# ID_logic.net
KiCad netlist of a schematic drawn in Altium Designer
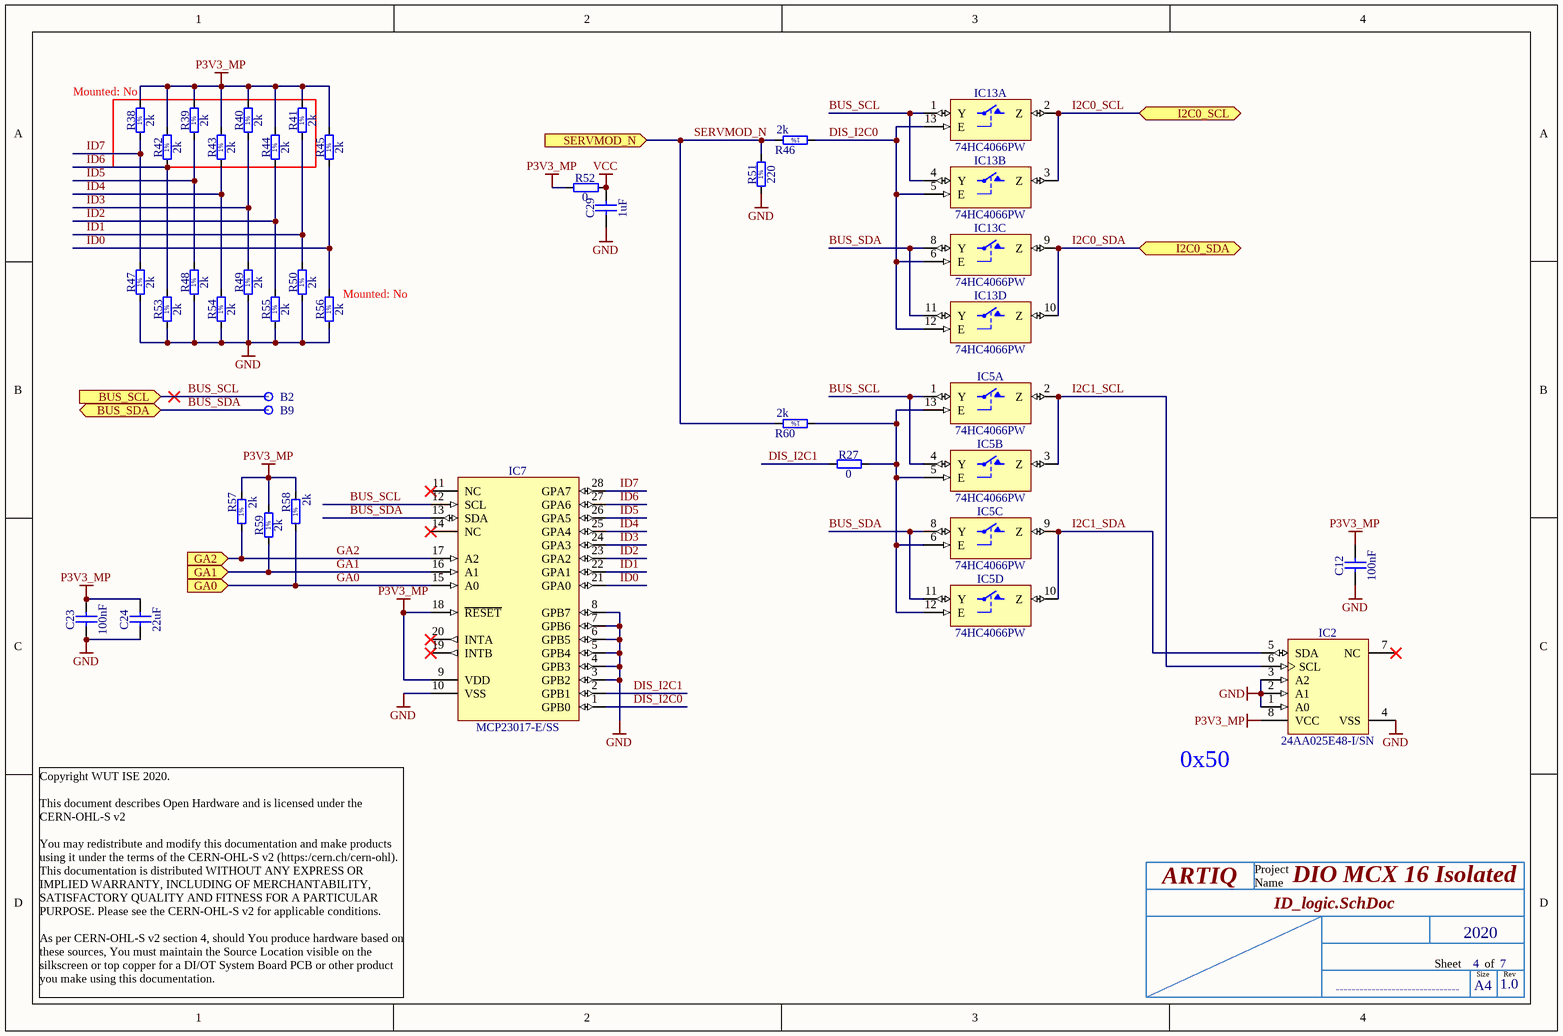
[diagram p0: ID_logic.SchDoc]

(export (version "E")
  (design (tool "Eeschema 10.0.6"))
  (components
    (comp (ref "B2")
      (value "Plated Hole")
      (footprint "c130h60")
      (description "Single Terminal Socket")
      (fields (field (name "PART NUMBER") "PLATED_HOLE0.6_PAD1.3") (field (name "AUTHOR") "CERN DEM MR"))
      (libsource (lib "Eletro-mechanical") (part "Single Terminal Socket"))
    )
    (comp (ref "B9")
      (value "Plated Hole")
      (footprint "c130h60")
      (description "Single Terminal Socket")
      (fields (field (name "PART NUMBER") "PLATED_HOLE0.6_PAD1.3") (field (name "AUTHOR") "CERN DEM MR"))
      (libsource (lib "Eletro-mechanical") (part "Single Terminal Socket"))
    )
    (comp (ref "C12")
      (value "100nF")
      (footprint "CAPC1005X55N")
      (description "Non-polarised capacitor")
      (fields
        (field (name "PART NUMBER") "CC0402_100NF_16V_10%_X5R")
        (field (name "VOLTAGE") "16V")
        (field (name "AUTHOR") "CERN DEM JLC")
      )
      (libsource (lib "Capacitors") (part "Capacitor - non polarized"))
    )
    (comp (ref "C23")
      (value "100nF")
      (footprint "CAPC1005X55N")
      (description "Non-polarised capacitor")
      (fields
        (field (name "PART NUMBER") "CC0402_100NF_16V_10%_X5R")
        (field (name "VOLTAGE") "16V")
        (field (name "AUTHOR") "CERN DEM JLC")
      )
      (libsource (lib "Capacitors") (part "Capacitor - non polarized"))
    )
    (comp (ref "C24")
      (value "22uF")
      (footprint "CAPC1709X100N")
      (description "Non-polarised capacitor")
      (fields
        (field (name "PART NUMBER") "CC0603_22UF_6.3V_20%_X5R")
        (field (name "VOLTAGE") "6.3V")
        (field (name "AUTHOR") "CERN DEM JLC")
      )
      (libsource (lib "Capacitors") (part "Capacitor - non polarized"))
    )
    (comp (ref "C29")
      (value "1uF")
      (footprint "CAPC2012X140N")
      (description "Non-polarised capacitor")
      (fields
        (field (name "PART NUMBER") "CC0805_1UF_35V_20%_X7R")
        (field (name "VOLTAGE") "35V")
        (field (name "AUTHOR") "CERN DEM JLC")
      )
      (libsource (lib "Capacitors") (part "Capacitor - non polarized"))
    )
    (comp (ref "IC2")
      (value "24AA025E48-I/SN")
      (footprint "SOIC127P600X175-8N")
      (description "1.7V-5.5V, 2K I2C™ Serial EEPROMs with EUI-48™ Node Identity")
      (fields (field (name "MANUFACTURER") "MICROCHIP TECHNOLOGY") (field (name "AUTHOR") "CERN DEM MR"))
      (libsource (lib "ICs And Semiconductors") (part "24AA025E48-I/SN"))
    )
    (comp (ref "IC5")
      (value "74HC4066PW")
      (footprint "SOP65P640X110-14N")
      (fields (field (name "MANUFACTURER") "NXP SEMICONDUCTORS") (field (name "AUTHOR") "CERN DEM JLC"))
      (libsource (lib "ICs And Semiconductors") (part "4066"))
    )
    (comp (ref "IC7")
      (value "MCP23017-E/SS")
      (footprint "SOP65P780X200-28N")
      (description "16-bit I/O Port Expander With Serial Interface")
      (fields (field (name "MANUFACTURER") "MICROCHIP TECHNOLOGY") (field (name "AUTHOR") "CERN DEM JLC"))
      (libsource (lib "ICs And Semiconductors") (part "MCP23017-E/SS"))
    )
    (comp (ref "IC13")
      (value "74HC4066PW")
      (footprint "SOP65P640X110-14N")
      (fields (field (name "MANUFACTURER") "NXP SEMICONDUCTORS") (field (name "AUTHOR") "CERN DEM JLC"))
      (libsource (lib "ICs And Semiconductors") (part "4066"))
    )
    (comp (ref "R27")
      (value "0")
      (footprint "RESC1005X40N")
      (description "Resistor")
      (fields
        (field (name "PART NUMBER") "R0402_0R_JUMPER")
        (field (name "MANUFACTURER") "GENERIC")
        (field (name "AUTHOR") "CERN DEM JLC")
      )
      (libsource (lib "Resistors") (part "Resistor"))
    )
    (comp (ref "R38")
      (value "2k")
      (footprint "RESC1608X55N")
      (description "Resistor - 1%")
      (fields
        (field (name "PART NUMBER") "R0603_2K_1%_0.1W_100PPM")
        (field (name "POWER") "0.1W")
        (field (name "MOUNTED") "No")
        (field (name "AUTHOR") "CERN DEM JLC")
      )
      (libsource (lib "Resistors") (part "Resistor - 1%"))
    )
    (comp (ref "R39")
      (value "2k")
      (footprint "RESC1608X55N")
      (description "Resistor - 1%")
      (fields
        (field (name "PART NUMBER") "R0603_2K_1%_0.1W_100PPM")
        (field (name "POWER") "0.1W")
        (field (name "AUTHOR") "CERN DEM JLC")
      )
      (libsource (lib "Resistors") (part "Resistor - 1%"))
    )
    (comp (ref "R40")
      (value "2k")
      (footprint "RESC1608X55N")
      (description "Resistor - 1%")
      (fields
        (field (name "PART NUMBER") "R0603_2K_1%_0.1W_100PPM")
        (field (name "POWER") "0.1W")
        (field (name "AUTHOR") "CERN DEM JLC")
      )
      (libsource (lib "Resistors") (part "Resistor - 1%"))
    )
    (comp (ref "R41")
      (value "2k")
      (footprint "RESC1608X55N")
      (description "Resistor - 1%")
      (fields
        (field (name "PART NUMBER") "R0603_2K_1%_0.1W_100PPM")
        (field (name "POWER") "0.1W")
        (field (name "AUTHOR") "CERN DEM JLC")
      )
      (libsource (lib "Resistors") (part "Resistor - 1%"))
    )
    (comp (ref "R42")
      (value "2k")
      (footprint "RESC1608X55N")
      (description "Resistor - 1%")
      (fields
        (field (name "PART NUMBER") "R0603_2K_1%_0.1W_100PPM")
        (field (name "POWER") "0.1W")
        (field (name "AUTHOR") "CERN DEM JLC")
      )
      (libsource (lib "Resistors") (part "Resistor - 1%"))
    )
    (comp (ref "R43")
      (value "2k")
      (footprint "RESC1608X55N")
      (description "Resistor - 1%")
      (fields
        (field (name "PART NUMBER") "R0603_2K_1%_0.1W_100PPM")
        (field (name "POWER") "0.1W")
        (field (name "AUTHOR") "CERN DEM JLC")
      )
      (libsource (lib "Resistors") (part "Resistor - 1%"))
    )
    (comp (ref "R44")
      (value "2k")
      (footprint "RESC1608X55N")
      (description "Resistor - 1%")
      (fields
        (field (name "PART NUMBER") "R0603_2K_1%_0.1W_100PPM")
        (field (name "POWER") "0.1W")
        (field (name "AUTHOR") "CERN DEM JLC")
      )
      (libsource (lib "Resistors") (part "Resistor - 1%"))
    )
    (comp (ref "R45")
      (value "2k")
      (footprint "RESC1608X55N")
      (description "Resistor - 1%")
      (fields
        (field (name "PART NUMBER") "R0603_2K_1%_0.1W_100PPM")
        (field (name "POWER") "0.1W")
        (field (name "AUTHOR") "CERN DEM JLC")
      )
      (libsource (lib "Resistors") (part "Resistor - 1%"))
    )
    (comp (ref "R46")
      (value "2k")
      (footprint "RESC1608X55N")
      (description "Resistor - 1%")
      (fields
        (field (name "PART NUMBER") "R0603_2K_1%_0.1W_100PPM")
        (field (name "POWER") "0.1W")
        (field (name "AUTHOR") "CERN DEM JLC")
      )
      (libsource (lib "Resistors") (part "Resistor - 1%"))
    )
    (comp (ref "R47")
      (value "2k")
      (footprint "RESC1608X55N")
      (description "Resistor - 1%")
      (fields
        (field (name "PART NUMBER") "R0603_2K_1%_0.1W_100PPM")
        (field (name "POWER") "0.1W")
        (field (name "AUTHOR") "CERN DEM JLC")
      )
      (libsource (lib "Resistors") (part "Resistor - 1%"))
    )
    (comp (ref "R48")
      (value "2k")
      (footprint "RESC1608X55N")
      (description "Resistor - 1%")
      (fields
        (field (name "PART NUMBER") "R0603_2K_1%_0.1W_100PPM")
        (field (name "POWER") "0.1W")
        (field (name "AUTHOR") "CERN DEM JLC")
      )
      (libsource (lib "Resistors") (part "Resistor - 1%"))
    )
    (comp (ref "R49")
      (value "2k")
      (footprint "RESC1608X55N")
      (description "Resistor - 1%")
      (fields
        (field (name "PART NUMBER") "R0603_2K_1%_0.1W_100PPM")
        (field (name "POWER") "0.1W")
        (field (name "AUTHOR") "CERN DEM JLC")
      )
      (libsource (lib "Resistors") (part "Resistor - 1%"))
    )
    (comp (ref "R50")
      (value "2k")
      (footprint "RESC1608X55N")
      (description "Resistor - 1%")
      (fields
        (field (name "PART NUMBER") "R0603_2K_1%_0.1W_100PPM")
        (field (name "POWER") "0.1W")
        (field (name "AUTHOR") "CERN DEM JLC")
      )
      (libsource (lib "Resistors") (part "Resistor - 1%"))
    )
    (comp (ref "R51")
      (value "220")
      (footprint "RESC1608X55N")
      (description "Resistor - 1%")
      (fields
        (field (name "PART NUMBER") "R0603_220R_1%_0.1W_100PPM")
        (field (name "POWER") "0.1W")
        (field (name "AUTHOR") "CERN DEM JLC")
      )
      (libsource (lib "Resistors") (part "Resistor - 1%"))
    )
    (comp (ref "R52")
      (value "0")
      (footprint "RESC1005X40N")
      (description "Resistor")
      (fields
        (field (name "PART NUMBER") "R0402_0R_JUMPER")
        (field (name "MANUFACTURER") "GENERIC")
        (field (name "AUTHOR") "CERN DEM JLC")
      )
      (libsource (lib "Resistors") (part "Resistor"))
    )
    (comp (ref "R53")
      (value "2k")
      (footprint "RESC1608X55N")
      (description "Resistor - 1%")
      (fields
        (field (name "PART NUMBER") "R0603_2K_1%_0.1W_100PPM")
        (field (name "POWER") "0.1W")
        (field (name "AUTHOR") "CERN DEM JLC")
      )
      (libsource (lib "Resistors") (part "Resistor - 1%"))
    )
    (comp (ref "R54")
      (value "2k")
      (footprint "RESC1608X55N")
      (description "Resistor - 1%")
      (fields
        (field (name "PART NUMBER") "R0603_2K_1%_0.1W_100PPM")
        (field (name "POWER") "0.1W")
        (field (name "AUTHOR") "CERN DEM JLC")
      )
      (libsource (lib "Resistors") (part "Resistor - 1%"))
    )
    (comp (ref "R55")
      (value "2k")
      (footprint "RESC1608X55N")
      (description "Resistor - 1%")
      (fields
        (field (name "PART NUMBER") "R0603_2K_1%_0.1W_100PPM")
        (field (name "POWER") "0.1W")
        (field (name "AUTHOR") "CERN DEM JLC")
      )
      (libsource (lib "Resistors") (part "Resistor - 1%"))
    )
    (comp (ref "R56")
      (value "2k")
      (footprint "RESC1608X55N")
      (description "Resistor - 1%")
      (fields
        (field (name "PART NUMBER") "R0603_2K_1%_0.1W_100PPM")
        (field (name "POWER") "0.1W")
        (field (name "MOUNTED") "No")
        (field (name "AUTHOR") "CERN DEM JLC")
      )
      (libsource (lib "Resistors") (part "Resistor - 1%"))
    )
    (comp (ref "R57")
      (value "2k")
      (footprint "RESC1608X55N")
      (description "Resistor - 1%")
      (fields
        (field (name "PART NUMBER") "R0603_2K_1%_0.1W_100PPM")
        (field (name "POWER") "0.1W")
        (field (name "AUTHOR") "CERN DEM JLC")
      )
      (libsource (lib "Resistors") (part "Resistor - 1%"))
    )
    (comp (ref "R58")
      (value "2k")
      (footprint "RESC1608X55N")
      (description "Resistor - 1%")
      (fields
        (field (name "PART NUMBER") "R0603_2K_1%_0.1W_100PPM")
        (field (name "POWER") "0.1W")
        (field (name "AUTHOR") "CERN DEM JLC")
      )
      (libsource (lib "Resistors") (part "Resistor - 1%"))
    )
    (comp (ref "R59")
      (value "2k")
      (footprint "RESC1608X55N")
      (description "Resistor - 1%")
      (fields
        (field (name "PART NUMBER") "R0603_2K_1%_0.1W_100PPM")
        (field (name "POWER") "0.1W")
        (field (name "AUTHOR") "CERN DEM JLC")
      )
      (libsource (lib "Resistors") (part "Resistor - 1%"))
    )
    (comp (ref "R60")
      (value "2k")
      (footprint "RESC1608X55N")
      (description "Resistor - 1%")
      (fields
        (field (name "PART NUMBER") "R0603_2K_1%_0.1W_100PPM")
        (field (name "POWER") "0.1W")
        (field (name "AUTHOR") "CERN DEM JLC")
      )
      (libsource (lib "Resistors") (part "Resistor - 1%"))
    )
  )
  (nets
    (net (code "1") (name "/BUS_SCL") (class "Default")
      (node (ref "B2") (pin "1") (pinfunction "1_1") (pintype "bidirectional"))
      (node (ref "IC13") (pin "1") (pinfunction "Y_1") (pintype "bidirectional"))
      (node (ref "IC13") (pin "4") (pinfunction "Y_4") (pintype "bidirectional"))
      (node (ref "IC5") (pin "1") (pinfunction "Y_1") (pintype "bidirectional"))
      (node (ref "IC5") (pin "4") (pinfunction "Y_4") (pintype "bidirectional"))
      (node (ref "IC7") (pin "12") (pinfunction "SCL_12") (pintype "input"))
    )
    (net (code "2") (name "/BUS_SDA") (class "Default")
      (node (ref "B9") (pin "1") (pinfunction "1_1") (pintype "bidirectional"))
      (node (ref "IC13") (pin "11") (pinfunction "Y_11") (pintype "bidirectional"))
      (node (ref "IC13") (pin "8") (pinfunction "Y_8") (pintype "bidirectional"))
      (node (ref "IC5") (pin "11") (pinfunction "Y_11") (pintype "bidirectional"))
      (node (ref "IC5") (pin "8") (pinfunction "Y_8") (pintype "bidirectional"))
      (node (ref "IC7") (pin "13") (pinfunction "SDA_13") (pintype "bidirectional"))
    )
    (net (code "3") (name "/DIS_I2C0") (class "Default")
      (node (ref "IC13") (pin "12") (pinfunction "E_12") (pintype "input"))
      (node (ref "IC13") (pin "13") (pinfunction "E_13") (pintype "input"))
      (node (ref "IC13") (pin "5") (pinfunction "E_5") (pintype "input"))
      (node (ref "IC13") (pin "6") (pinfunction "E_6") (pintype "input"))
      (node (ref "IC7") (pin "1") (pinfunction "GPB0_1") (pintype "bidirectional"))
      (node (ref "R46") (pin "1") (pinfunction "1_1") (pintype "passive"))
    )
    (net (code "4") (name "/DIS_I2C1") (class "Default")
      (node (ref "IC7") (pin "2") (pinfunction "GPB1_2") (pintype "bidirectional"))
      (node (ref "R27") (pin "1") (pinfunction "1_1") (pintype "passive"))
    )
    (net (code "5") (name "/GA0") (class "Default")
      (node (ref "IC7") (pin "15") (pinfunction "A0_15") (pintype "input"))
      (node (ref "R58") (pin "1") (pinfunction "1_1") (pintype "passive"))
    )
    (net (code "6") (name "/GA1") (class "Default")
      (node (ref "IC7") (pin "16") (pinfunction "A1_16") (pintype "input"))
      (node (ref "R59") (pin "1") (pinfunction "1_1") (pintype "passive"))
    )
    (net (code "7") (name "/GA2") (class "Default")
      (node (ref "IC7") (pin "17") (pinfunction "A2_17") (pintype "input"))
      (node (ref "R57") (pin "1") (pinfunction "1_1") (pintype "passive"))
    )
    (net (code "8") (name "/I2C0_SCL") (class "Default")
      (node (ref "IC13") (pin "2") (pinfunction "Z_2") (pintype "bidirectional"))
      (node (ref "IC13") (pin "3") (pinfunction "Z_3") (pintype "bidirectional"))
    )
    (net (code "9") (name "/I2C0_SDA") (class "Default")
      (node (ref "IC13") (pin "10") (pinfunction "Z_10") (pintype "bidirectional"))
      (node (ref "IC13") (pin "9") (pinfunction "Z_9") (pintype "bidirectional"))
    )
    (net (code "10") (name "/I2C1_SCL") (class "Default")
      (node (ref "IC2") (pin "6") (pinfunction "SCL_6") (pintype "input"))
      (node (ref "IC5") (pin "2") (pinfunction "Z_2") (pintype "bidirectional"))
      (node (ref "IC5") (pin "3") (pinfunction "Z_3") (pintype "bidirectional"))
    )
    (net (code "11") (name "/I2C1_SDA") (class "Default")
      (node (ref "IC2") (pin "5") (pinfunction "SDA_5") (pintype "bidirectional"))
      (node (ref "IC5") (pin "10") (pinfunction "Z_10") (pintype "bidirectional"))
      (node (ref "IC5") (pin "9") (pinfunction "Z_9") (pintype "bidirectional"))
    )
    (net (code "12") (name "/ID0") (class "Default")
      (node (ref "IC7") (pin "21") (pinfunction "GPA0_21") (pintype "bidirectional"))
      (node (ref "R45") (pin "1") (pinfunction "1_1") (pintype "passive"))
      (node (ref "R56") (pin "2") (pinfunction "2_2") (pintype "passive"))
    )
    (net (code "13") (name "/ID1") (class "Default")
      (node (ref "IC7") (pin "22") (pinfunction "GPA1_22") (pintype "bidirectional"))
      (node (ref "R41") (pin "1") (pinfunction "1_1") (pintype "passive"))
      (node (ref "R50") (pin "2") (pinfunction "2_2") (pintype "passive"))
    )
    (net (code "14") (name "/ID2") (class "Default")
      (node (ref "IC7") (pin "23") (pinfunction "GPA2_23") (pintype "bidirectional"))
      (node (ref "R44") (pin "1") (pinfunction "1_1") (pintype "passive"))
      (node (ref "R55") (pin "2") (pinfunction "2_2") (pintype "passive"))
    )
    (net (code "15") (name "/ID3") (class "Default")
      (node (ref "IC7") (pin "24") (pinfunction "GPA3_24") (pintype "bidirectional"))
      (node (ref "R40") (pin "1") (pinfunction "1_1") (pintype "passive"))
      (node (ref "R49") (pin "2") (pinfunction "2_2") (pintype "passive"))
    )
    (net (code "16") (name "/ID4") (class "Default")
      (node (ref "IC7") (pin "25") (pinfunction "GPA4_25") (pintype "bidirectional"))
      (node (ref "R43") (pin "1") (pinfunction "1_1") (pintype "passive"))
      (node (ref "R54") (pin "2") (pinfunction "2_2") (pintype "passive"))
    )
    (net (code "17") (name "/ID5") (class "Default")
      (node (ref "IC7") (pin "26") (pinfunction "GPA5_26") (pintype "bidirectional"))
      (node (ref "R39") (pin "1") (pinfunction "1_1") (pintype "passive"))
      (node (ref "R48") (pin "2") (pinfunction "2_2") (pintype "passive"))
    )
    (net (code "18") (name "/ID6") (class "Default")
      (node (ref "IC7") (pin "27") (pinfunction "GPA6_27") (pintype "bidirectional"))
      (node (ref "R42") (pin "1") (pinfunction "1_1") (pintype "passive"))
      (node (ref "R53") (pin "2") (pinfunction "2_2") (pintype "passive"))
    )
    (net (code "19") (name "/ID7") (class "Default")
      (node (ref "IC7") (pin "28") (pinfunction "GPA7_28") (pintype "bidirectional"))
      (node (ref "R38") (pin "1") (pinfunction "1_1") (pintype "passive"))
      (node (ref "R47") (pin "2") (pinfunction "2_2") (pintype "passive"))
    )
    (net (code "20") (name "/SERVMOD_N") (class "Default")
      (node (ref "R46") (pin "2") (pinfunction "2_2") (pintype "passive"))
      (node (ref "R51") (pin "2") (pinfunction "2_2") (pintype "passive"))
      (node (ref "R60") (pin "2") (pinfunction "2_2") (pintype "passive"))
    )
    (net (code "21") (name "GND") (class "Default")
      (node (ref "C12") (pin "1") (pinfunction "1_1") (pintype "passive"))
      (node (ref "C23") (pin "1") (pinfunction "1_1") (pintype "passive"))
      (node (ref "C24") (pin "1") (pinfunction "1_1") (pintype "passive"))
      (node (ref "C29") (pin "1") (pinfunction "1_1") (pintype "passive"))
      (node (ref "IC13") (pin "7") (pinfunction "GND_7") (pintype "power_in"))
      (node (ref "IC2") (pin "1") (pinfunction "A0_1") (pintype "input"))
      (node (ref "IC2") (pin "2") (pinfunction "A1_2") (pintype "input"))
      (node (ref "IC2") (pin "3") (pinfunction "A2_3") (pintype "input"))
      (node (ref "IC2") (pin "4") (pinfunction "VSS_4") (pintype "power_in"))
      (node (ref "IC5") (pin "7") (pinfunction "GND_7") (pintype "power_in"))
      (node (ref "IC7") (pin "10") (pinfunction "VSS_10") (pintype "power_in"))
      (node (ref "IC7") (pin "3") (pinfunction "GPB2_3") (pintype "bidirectional"))
      (node (ref "IC7") (pin "4") (pinfunction "GPB3_4") (pintype "bidirectional"))
      (node (ref "IC7") (pin "5") (pinfunction "GPB4_5") (pintype "bidirectional"))
      (node (ref "IC7") (pin "6") (pinfunction "GPB5_6") (pintype "bidirectional"))
      (node (ref "IC7") (pin "7") (pinfunction "GPB6_7") (pintype "bidirectional"))
      (node (ref "IC7") (pin "8") (pinfunction "GPB7_8") (pintype "bidirectional"))
      (node (ref "R47") (pin "1") (pinfunction "1_1") (pintype "passive"))
      (node (ref "R48") (pin "1") (pinfunction "1_1") (pintype "passive"))
      (node (ref "R49") (pin "1") (pinfunction "1_1") (pintype "passive"))
      (node (ref "R50") (pin "1") (pinfunction "1_1") (pintype "passive"))
      (node (ref "R51") (pin "1") (pinfunction "1_1") (pintype "passive"))
      (node (ref "R53") (pin "1") (pinfunction "1_1") (pintype "passive"))
      (node (ref "R54") (pin "1") (pinfunction "1_1") (pintype "passive"))
      (node (ref "R55") (pin "1") (pinfunction "1_1") (pintype "passive"))
      (node (ref "R56") (pin "1") (pinfunction "1_1") (pintype "passive"))
    )
    (net (code "22") (name "Net-(IC5A-E)") (class "Default")
      (node (ref "IC5") (pin "12") (pinfunction "E_12") (pintype "input"))
      (node (ref "IC5") (pin "13") (pinfunction "E_13") (pintype "input"))
      (node (ref "IC5") (pin "5") (pinfunction "E_5") (pintype "input"))
      (node (ref "IC5") (pin "6") (pinfunction "E_6") (pintype "input"))
      (node (ref "R27") (pin "2") (pinfunction "2_2") (pintype "passive"))
      (node (ref "R60") (pin "1") (pinfunction "1_1") (pintype "passive"))
    )
    (net (code "23") (name "P3V3_MP") (class "Default")
      (node (ref "C12") (pin "2") (pinfunction "2_2") (pintype "passive"))
      (node (ref "C23") (pin "2") (pinfunction "2_2") (pintype "passive"))
      (node (ref "C24") (pin "2") (pinfunction "2_2") (pintype "passive"))
      (node (ref "IC2") (pin "8") (pinfunction "VCC_8") (pintype "power_in"))
      (node (ref "IC7") (pin "18") (pinfunction "~{RESET}_18") (pintype "input"))
      (node (ref "IC7") (pin "9") (pinfunction "VDD_9") (pintype "power_in"))
      (node (ref "R38") (pin "2") (pinfunction "2_2") (pintype "passive"))
      (node (ref "R39") (pin "2") (pinfunction "2_2") (pintype "passive"))
      (node (ref "R40") (pin "2") (pinfunction "2_2") (pintype "passive"))
      (node (ref "R41") (pin "2") (pinfunction "2_2") (pintype "passive"))
      (node (ref "R42") (pin "2") (pinfunction "2_2") (pintype "passive"))
      (node (ref "R43") (pin "2") (pinfunction "2_2") (pintype "passive"))
      (node (ref "R44") (pin "2") (pinfunction "2_2") (pintype "passive"))
      (node (ref "R45") (pin "2") (pinfunction "2_2") (pintype "passive"))
      (node (ref "R52") (pin "1") (pinfunction "1_1") (pintype "passive"))
      (node (ref "R57") (pin "2") (pinfunction "2_2") (pintype "passive"))
      (node (ref "R58") (pin "2") (pinfunction "2_2") (pintype "passive"))
      (node (ref "R59") (pin "2") (pinfunction "2_2") (pintype "passive"))
    )
    (net (code "24") (name "VCC") (class "Default")
      (node (ref "C29") (pin "2") (pinfunction "2_2") (pintype "passive"))
      (node (ref "IC13") (pin "14") (pinfunction "VCC_14") (pintype "power_in"))
      (node (ref "IC5") (pin "14") (pinfunction "VCC_14") (pintype "power_in"))
      (node (ref "R52") (pin "2") (pinfunction "2_2") (pintype "passive"))
    )
    (net (code "25") (name "unconnected-(IC2-NC-Pad7)") (class "Default")
      (node (ref "IC2") (pin "7") (pinfunction "NC_7") (pintype "passive+no_connect"))
    )
    (net (code "26") (name "unconnected-(IC7-INTA-Pad20)") (class "Default")
      (node (ref "IC7") (pin "20") (pinfunction "INTA_20") (pintype "output+no_connect"))
    )
    (net (code "27") (name "unconnected-(IC7-INTB-Pad19)") (class "Default")
      (node (ref "IC7") (pin "19") (pinfunction "INTB_19") (pintype "output+no_connect"))
    )
    (net (code "28") (name "unconnected-(IC7-NC-Pad11)") (class "Default")
      (node (ref "IC7") (pin "11") (pinfunction "NC_11") (pintype "passive+no_connect"))
    )
    (net (code "29") (name "unconnected-(IC7-NC-Pad14)") (class "Default")
      (node (ref "IC7") (pin "14") (pinfunction "NC_14") (pintype "passive+no_connect"))
    )
  )
)
